# OptoTest.net
KiCad netlist of a schematic drawn in EAGLE
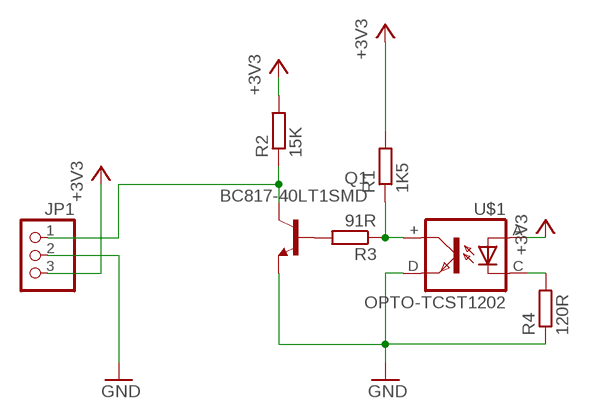
[diagram p0: schematic, sheet 1]

(export (version "E")
  (design (tool "Eeschema 10.0.6"))
  (components
    (comp (ref "JP1")
      (value "PINHD-1X3/90")
      (footprint "eagle-import:1X03_90")
      (libsource (lib "eagle-import") (part "PINHD-1X3/90"))
    )
    (comp (ref "Q1")
      (value "BC817-40LT1SMD")
      (footprint "eagle-import:SOT23-BEC")
      (libsource (lib "eagle-import") (part "BC817SMD-40LT1"))
    )
    (comp (ref "R1")
      (value "1K5")
      (footprint "eagle-import:R0805")
      (libsource (lib "eagle-import") (part "R_0805"))
    )
    (comp (ref "R2")
      (value "15K")
      (footprint "eagle-import:R0805")
      (libsource (lib "eagle-import") (part "R_0805"))
    )
    (comp (ref "R3")
      (value "91R")
      (footprint "eagle-import:R0805")
      (libsource (lib "eagle-import") (part "R_0805"))
    )
    (comp (ref "R4")
      (value "120R")
      (footprint "eagle-import:R0805")
      (libsource (lib "eagle-import") (part "R_0805"))
    )
    (comp (ref "U$1")
      (value "OPTO-TCST1202")
      (footprint "eagle-import:TCST1202")
      (libsource (lib "eagle-import") (part "OPTO-TCST1202"))
    )
  )
  (nets
    (net (code "1") (name "+3V3") (class "Default")
      (node (ref "JP1") (pin "3") (pinfunction "3_3") (pintype "passive"))
      (node (ref "R1") (pin "2") (pinfunction "2_2") (pintype "passive"))
      (node (ref "R2") (pin "2") (pinfunction "2_2") (pintype "passive"))
      (node (ref "U$1") (pin "A") (pinfunction "A_A") (pintype "passive"))
    )
    (net (code "2") (name "GND") (class "Default")
      (node (ref "JP1") (pin "2") (pinfunction "2_2") (pintype "passive"))
      (node (ref "Q1") (pin "E") (pinfunction "E_E") (pintype "passive"))
      (node (ref "R4") (pin "1") (pinfunction "1_1") (pintype "passive"))
      (node (ref "U$1") (pin "D") (pinfunction "EMIT_D") (pintype "passive"))
    )
    (net (code "3") (name "Net-(JP1-Pad1)") (class "Default")
      (node (ref "JP1") (pin "1") (pinfunction "1_1") (pintype "passive"))
      (node (ref "Q1") (pin "C") (pinfunction "C_C") (pintype "passive"))
      (node (ref "R2") (pin "1") (pinfunction "1_1") (pintype "passive"))
    )
    (net (code "4") (name "Net-(Q1-PadB)") (class "Default")
      (node (ref "Q1") (pin "B") (pinfunction "B_B") (pintype "passive"))
      (node (ref "R3") (pin "2") (pinfunction "2_2") (pintype "passive"))
    )
    (net (code "5") (name "Net-(R4-Pad2)") (class "Default")
      (node (ref "R4") (pin "2") (pinfunction "2_2") (pintype "passive"))
      (node (ref "U$1") (pin "C") (pinfunction "C_C") (pintype "passive"))
    )
    (net (code "6") (name "Net-(U$1-COL)") (class "Default")
      (node (ref "R1") (pin "1") (pinfunction "1_1") (pintype "passive"))
      (node (ref "R3") (pin "1") (pinfunction "1_1") (pintype "passive"))
      (node (ref "U$1") (pin "+") (pinfunction "COL_+") (pintype "passive"))
    )
  )
)
